# DI_DO.net
KiCad netlist of a schematic drawn in Altium Designer
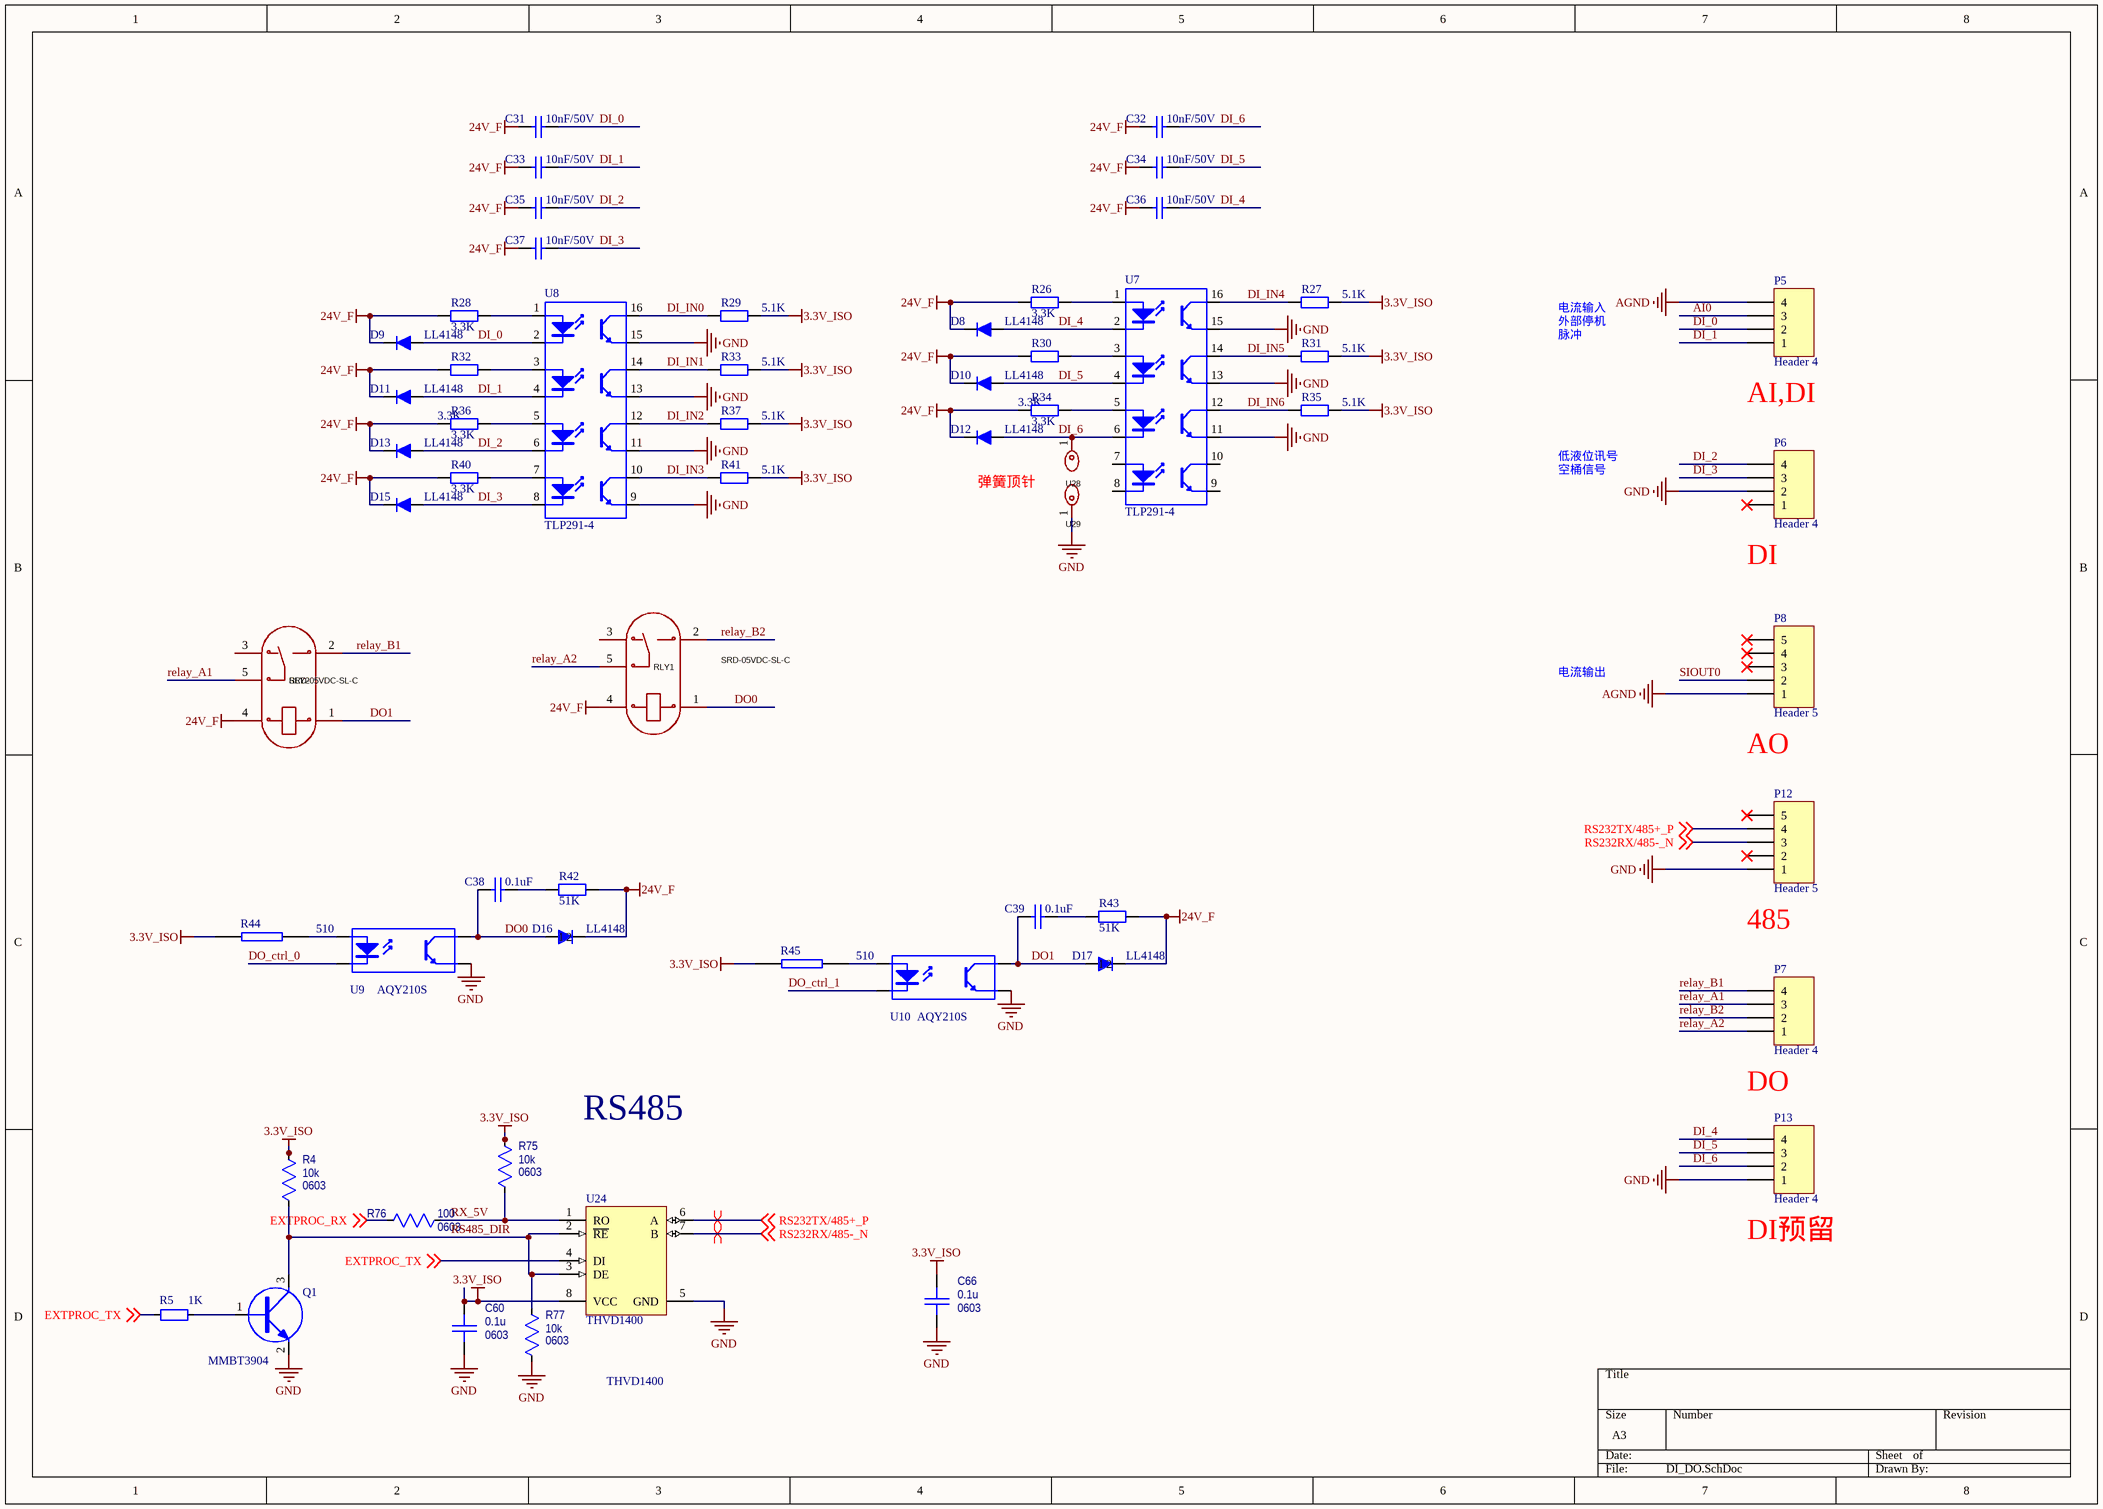
[diagram p0: DI_DO.SchDoc]

(export (version "E")
  (design (tool "Eeschema 10.0.6"))
  (components
    (comp (ref "C31")
      (value "10nF/50V")
      (footprint "0603C")
      (description "Capacitor")
      (fields (field (name "PUBLISHER") "Altium Limited"))
      (libsource (lib "Miscellaneous Devices") (part "Cap"))
    )
    (comp (ref "C32")
      (value "10nF/50V")
      (footprint "0603C")
      (description "Capacitor")
      (fields (field (name "PUBLISHER") "Altium Limited"))
      (libsource (lib "Miscellaneous Devices") (part "Cap"))
    )
    (comp (ref "C33")
      (value "10nF/50V")
      (footprint "0603C")
      (description "Capacitor")
      (fields (field (name "PUBLISHER") "Altium Limited"))
      (libsource (lib "Miscellaneous Devices") (part "Cap"))
    )
    (comp (ref "C34")
      (value "10nF/50V")
      (footprint "0603C")
      (description "Capacitor")
      (fields (field (name "PUBLISHER") "Altium Limited"))
      (libsource (lib "Miscellaneous Devices") (part "Cap"))
    )
    (comp (ref "C35")
      (value "10nF/50V")
      (footprint "0603C")
      (description "Capacitor")
      (fields (field (name "PUBLISHER") "Altium Limited"))
      (libsource (lib "Miscellaneous Devices") (part "Cap"))
    )
    (comp (ref "C36")
      (value "10nF/50V")
      (footprint "0603C")
      (description "Capacitor")
      (fields (field (name "PUBLISHER") "Altium Limited"))
      (libsource (lib "Miscellaneous Devices") (part "Cap"))
    )
    (comp (ref "C37")
      (value "10nF/50V")
      (footprint "0603C")
      (description "Capacitor")
      (fields (field (name "PUBLISHER") "Altium Limited"))
      (libsource (lib "Miscellaneous Devices") (part "Cap"))
    )
    (comp (ref "C38")
      (value "0.1uF")
      (footprint "0603C")
      (description "Capacitor")
      (libsource (lib "*") (part "CAP"))
    )
    (comp (ref "C39")
      (value "0.1uF")
      (footprint "0603C")
      (description "Capacitor")
      (libsource (lib "*") (part "CAP"))
    )
    (comp (ref "C60")
      (value "0.1u")
      (footprint "CAPC1608X092N_0603")
      (description "Capacitor, MLCC")
      (fields
        (field (name "PARTNUMBER") "C0603C104M5RACTU")
        (field (name "TOLERANCE") "[tol]")
        (field (name "PACKAGE") "0603")
      )
      (libsource (lib "Karl") (part "Capacitor_0603"))
    )
    (comp (ref "C66")
      (value "0.1u")
      (footprint "CAPC1608X092N_0603")
      (description "Capacitor, MLCC")
      (fields
        (field (name "PARTNUMBER") "C0603C104M5RACTU")
        (field (name "TOLERANCE") "[tol]")
        (field (name "PACKAGE") "0603")
      )
      (libsource (lib "Karl") (part "Capacitor_0603"))
    )
    (comp (ref "D8")
      (value "LL4148")
      (footprint "DO-213AB/LL34/MiniMELF")
      (description "VISHAY,LL4148,圆柱体MiniMELF100V/2A,ROHS")
      (libsource (lib "Device2018") (part "LL4148"))
    )
    (comp (ref "D9")
      (value "LL4148")
      (footprint "DO-213AB/LL34/MiniMELF")
      (description "VISHAY,LL4148,圆柱体MiniMELF100V/2A,ROHS")
      (libsource (lib "Device2018") (part "LL4148"))
    )
    (comp (ref "D10")
      (value "LL4148")
      (footprint "DO-213AB/LL34/MiniMELF")
      (description "VISHAY,LL4148,圆柱体MiniMELF100V/2A,ROHS")
      (libsource (lib "Device2018") (part "LL4148"))
    )
    (comp (ref "D11")
      (value "LL4148")
      (footprint "DO-213AB/LL34/MiniMELF")
      (description "VISHAY,LL4148,圆柱体MiniMELF100V/2A,ROHS")
      (libsource (lib "Device2018") (part "LL4148"))
    )
    (comp (ref "D12")
      (value "LL4148")
      (footprint "DO-213AB/LL34/MiniMELF")
      (description "VISHAY,LL4148,圆柱体MiniMELF100V/2A,ROHS")
      (libsource (lib "Device2018") (part "LL4148"))
    )
    (comp (ref "D13")
      (value "LL4148")
      (footprint "DO-213AB/LL34/MiniMELF")
      (description "VISHAY,LL4148,圆柱体MiniMELF100V/2A,ROHS")
      (libsource (lib "Device2018") (part "LL4148"))
    )
    (comp (ref "D15")
      (value "LL4148")
      (footprint "DO-213AB/LL34/MiniMELF")
      (description "VISHAY,LL4148,圆柱体MiniMELF100V/2A,ROHS")
      (libsource (lib "Device2018") (part "LL4148"))
    )
    (comp (ref "D16")
      (value "LL4148")
      (footprint "DO-213AB/LL34/MiniMELF")
      (description "VISHAY,LL4148,圆柱体MiniMELF100V/2A,ROHS")
      (libsource (lib "") (part "LL4148_1"))
    )
    (comp (ref "D17")
      (value "LL4148")
      (footprint "DO-213AB/LL34/MiniMELF")
      (description "VISHAY,LL4148,圆柱体MiniMELF100V/2A,ROHS")
      (libsource (lib "") (part "LL4148_1"))
    )
    (comp (ref "P5")
      (value "Header 4")
      (footprint "CONN#PH2.0-4A")
      (description "Header, 4-Pin")
      (fields (field (name "PUBLISHER") "Altium Limited"))
      (libsource (lib "Miscellaneous Connectors") (part "Header 4"))
    )
    (comp (ref "P6")
      (value "Header 4")
      (footprint "CONN#PH2.0-4A")
      (description "Header, 4-Pin")
      (fields (field (name "PUBLISHER") "Altium Limited"))
      (libsource (lib "Miscellaneous Connectors") (part "Header 4"))
    )
    (comp (ref "P7")
      (value "Header 4")
      (footprint "CONN#PH2.0-4A")
      (description "Header, 4-Pin")
      (fields (field (name "PUBLISHER") "Altium Limited"))
      (libsource (lib "Miscellaneous Connectors") (part "Header 4"))
    )
    (comp (ref "P8")
      (value "Header 5")
      (footprint "CONN#PH2.0-5A")
      (description "Header, 5-Pin")
      (fields (field (name "PUBLISHER") "Altium Limited"))
      (libsource (lib "Miscellaneous Connectors") (part "Header 5"))
    )
    (comp (ref "P12")
      (value "Header 5")
      (footprint "CONN#PH2.0-5A")
      (description "Header, 5-Pin")
      (fields (field (name "PUBLISHER") "Altium Limited"))
      (libsource (lib "Miscellaneous Connectors") (part "Header 5"))
    )
    (comp (ref "P13")
      (value "Header 4")
      (footprint "CONN#PH2.0-4A")
      (description "Header, 4-Pin")
      (fields (field (name "PUBLISHER") "Altium Limited"))
      (libsource (lib "Miscellaneous Connectors") (part "Header 4"))
    )
    (comp (ref "Q1")
      (value "MMBT3904")
      (footprint "SOT23-3")
      (libsource (lib "CenLib") (part "NPN_MMBT3904"))
    )
    (comp (ref "R4")
      (value "10k")
      (footprint "RESC1608X055N_0603")
      (description "Resistor, Standard")
      (fields
        (field (name "PARTNUMBER") "RC0603FR-0710KL")
        (field (name "TOLERANCE") "tol")
        (field (name "PACKAGE") "0603")
      )
      (libsource (lib "Karl") (part "Resistor_0603"))
    )
    (comp (ref "R5") (value "1K") (footprint "0603r") (libsource (lib "RC_M_D_00") (part "RES0603")))
    (comp (ref "R26") (value "3.3K") (footprint "0603R") (libsource (lib "MQlibrary") (part "Res0805M")))
    (comp (ref "R27") (value "5.1K") (footprint "0603R") (libsource (lib "MQlibrary") (part "Res0805M")))
    (comp (ref "R28") (value "3.3K") (footprint "0603R") (libsource (lib "MQlibrary") (part "Res0805M")))
    (comp (ref "R29") (value "5.1K") (footprint "0603R") (libsource (lib "MQlibrary") (part "Res0805M")))
    (comp (ref "R30") (value "3.3K") (footprint "0603R") (libsource (lib "MQlibrary") (part "Res0805M")))
    (comp (ref "R31") (value "5.1K") (footprint "0603R") (libsource (lib "MQlibrary") (part "Res0805M")))
    (comp (ref "R32") (value "3.3K") (footprint "0603R") (libsource (lib "MQlibrary") (part "Res0805M")))
    (comp (ref "R33") (value "5.1K") (footprint "0603R") (libsource (lib "MQlibrary") (part "Res0805M")))
    (comp (ref "R34") (value "3.3K") (footprint "0603R") (libsource (lib "MQlibrary") (part "Res0805M")))
    (comp (ref "R35") (value "5.1K") (footprint "0603R") (libsource (lib "MQlibrary") (part "Res0805M")))
    (comp (ref "R36") (value "3.3K") (footprint "0603R") (libsource (lib "MQlibrary") (part "Res0805M")))
    (comp (ref "R37") (value "5.1K") (footprint "0603R") (libsource (lib "MQlibrary") (part "Res0805M")))
    (comp (ref "R40") (value "3.3K") (footprint "0603R") (libsource (lib "MQlibrary") (part "Res0805M")))
    (comp (ref "R41") (value "5.1K") (footprint "0603R") (libsource (lib "MQlibrary") (part "Res0805M")))
    (comp (ref "R42") (value "51K") (footprint "0603R") (libsource (lib "") (part "Res0805M_1")))
    (comp (ref "R43") (value "51K") (footprint "0603R") (libsource (lib "") (part "Res0805M_1")))
    (comp (ref "R44") (value "510") (footprint "0603R") (libsource (lib "*") (part "RES2")))
    (comp (ref "R45") (value "510") (footprint "0603R") (libsource (lib "*") (part "RES2")))
    (comp (ref "R75")
      (value "10k")
      (footprint "RESC1608X055N_0603")
      (description "Resistor, Standard")
      (fields
        (field (name "PARTNUMBER") "RC0603FR-0710KL")
        (field (name "TOLERANCE") "tol")
        (field (name "PACKAGE") "0603")
      )
      (libsource (lib "Karl") (part "Resistor_0603"))
    )
    (comp (ref "R76")
      (value "100")
      (footprint "RESC1608X055N_0603")
      (description "Resistor, Standard")
      (fields
        (field (name "PARTNUMBER") "RC0603FR-07100RL")
        (field (name "TOLERANCE") "tol")
        (field (name "PACKAGE") "0603")
      )
      (libsource (lib "Karl") (part "Resistor_0603"))
    )
    (comp (ref "R77")
      (value "10k")
      (footprint "RESC1608X055N_0603")
      (description "Resistor, Standard")
      (fields
        (field (name "PARTNUMBER") "RC0603FR-0710KL")
        (field (name "TOLERANCE") "tol")
        (field (name "PACKAGE") "0603")
      )
      (libsource (lib "Karl") (part "Resistor_0603"))
    )
    (comp (ref "RLY1")
      (value "SRD-05VDC-SL-C")
      (footprint "RELAY-TH_SRD-XXVDC-XL-C")
      (fields (field (name "MANUFACTURER") "松乐"))
      (libsource (lib "altium-import") (part "root_0_SRD-05VDC-SL-C_"))
    )
    (comp (ref "RLY2")
      (value "SRD-05VDC-SL-C")
      (footprint "RELAY-TH_SRD-XXVDC-XL-C")
      (fields (field (name "MANUFACTURER") "松乐"))
      (libsource (lib "altium-import") (part "root_0_SRD-05VDC-SL-C_"))
    )
    (comp (ref "U7") (value "TLP291-4") (footprint "SOP16-T") (libsource (lib "DI16") (part "TLP281-4")))
    (comp (ref "U8") (value "TLP291-4") (footprint "SOP16-T") (libsource (lib "DI16") (part "TLP281-4")))
    (comp (ref "U9")
      (value "AQY210S")
      (footprint "sop4")
      (description "4-Pin Phototransistor Optocoupler")
      (fields (field (name "PUBLISHER") "Altium Limited"))
      (libsource (lib "Miscellaneous Devices") (part "Optoisolator1"))
    )
    (comp (ref "U10")
      (value "AQY210S")
      (footprint "sop4")
      (description "4-Pin Phototransistor Optocoupler")
      (fields (field (name "PUBLISHER") "Altium Limited"))
      (libsource (lib "Miscellaneous Devices") (part "Optoisolator1"))
    )
    (comp (ref "U24")
      (value "THVD1400")
      (footprint "MAXM-S8+4_M")
      (fields (field (name "PARTNUMBER") "MAX33071EASA+"))
      (libsource (lib "Bogen") (part "MAX33071EASA+"))
    )
    (comp (ref "U28")
      (value "YTC1P-3015-01")
      (footprint "CONN-SMD_YTC1P-3015-01")
      (fields (field (name "MANUFACTURER") "YIYUAN(怡远)"))
      (libsource (lib "Flow_Pump") (part "YTC1P-3015-01"))
    )
    (comp (ref "U29")
      (value "YTC1P-3015-01")
      (footprint "CONN-SMD_YTC1P-3015-01")
      (fields (field (name "MANUFACTURER") "YIYUAN(怡远)"))
      (libsource (lib "Flow_Pump") (part "YTC1P-3015-01"))
    )
  )
  (nets
    (net (code "1") (name "/AI0") (class "Default")
      (node (ref "P5") (pin "3") (pinfunction "3_3") (pintype "passive"))
    )
    (net (code "2") (name "/DI_0") (class "Default")
      (node (ref "C31") (pin "2") (pinfunction "2_2") (pintype "passive"))
      (node (ref "D9") (pin "1") (pinfunction "2_1") (pintype "passive"))
      (node (ref "P5") (pin "2") (pinfunction "2_2") (pintype "passive"))
      (node (ref "U8") (pin "2") (pinfunction "K_2") (pintype "passive"))
    )
    (net (code "3") (name "/DI_1") (class "Default")
      (node (ref "C33") (pin "2") (pinfunction "2_2") (pintype "passive"))
      (node (ref "D11") (pin "1") (pinfunction "2_1") (pintype "passive"))
      (node (ref "P5") (pin "1") (pinfunction "1_1") (pintype "passive"))
      (node (ref "U8") (pin "4") (pinfunction "K_4") (pintype "passive"))
    )
    (net (code "4") (name "/DI_2") (class "Default")
      (node (ref "C35") (pin "2") (pinfunction "2_2") (pintype "passive"))
      (node (ref "D13") (pin "1") (pinfunction "2_1") (pintype "passive"))
      (node (ref "P6") (pin "4") (pinfunction "4_4") (pintype "passive"))
      (node (ref "U8") (pin "6") (pinfunction "K_6") (pintype "passive"))
    )
    (net (code "5") (name "/DI_3") (class "Default")
      (node (ref "C37") (pin "2") (pinfunction "2_2") (pintype "passive"))
      (node (ref "D15") (pin "1") (pinfunction "2_1") (pintype "passive"))
      (node (ref "P6") (pin "3") (pinfunction "3_3") (pintype "passive"))
      (node (ref "U8") (pin "8") (pinfunction "K_8") (pintype "passive"))
    )
    (net (code "6") (name "/DI_4") (class "Default")
      (node (ref "C36") (pin "2") (pinfunction "2_2") (pintype "passive"))
      (node (ref "D8") (pin "1") (pinfunction "2_1") (pintype "passive"))
      (node (ref "P13") (pin "4") (pinfunction "4_4") (pintype "passive"))
      (node (ref "U7") (pin "2") (pinfunction "K_2") (pintype "passive"))
    )
    (net (code "7") (name "/DI_5") (class "Default")
      (node (ref "C34") (pin "2") (pinfunction "2_2") (pintype "passive"))
      (node (ref "D10") (pin "1") (pinfunction "2_1") (pintype "passive"))
      (node (ref "P13") (pin "3") (pinfunction "3_3") (pintype "passive"))
      (node (ref "U7") (pin "4") (pinfunction "K_4") (pintype "passive"))
    )
    (net (code "8") (name "/DI_6") (class "Default")
      (node (ref "C32") (pin "2") (pinfunction "2_2") (pintype "passive"))
      (node (ref "D12") (pin "1") (pinfunction "2_1") (pintype "passive"))
      (node (ref "P13") (pin "2") (pinfunction "2_2") (pintype "passive"))
      (node (ref "U28") (pin "1") (pinfunction "1_1") (pintype "passive"))
      (node (ref "U7") (pin "6") (pinfunction "K_6") (pintype "passive"))
    )
    (net (code "9") (name "/DI_IN0") (class "Default")
      (node (ref "R29") (pin "2") (pinfunction "2_2") (pintype "passive"))
      (node (ref "U8") (pin "16") (pinfunction "C_16") (pintype "passive"))
    )
    (net (code "10") (name "/DI_IN1") (class "Default")
      (node (ref "R33") (pin "2") (pinfunction "2_2") (pintype "passive"))
      (node (ref "U8") (pin "14") (pinfunction "C_14") (pintype "passive"))
    )
    (net (code "11") (name "/DI_IN2") (class "Default")
      (node (ref "R37") (pin "2") (pinfunction "2_2") (pintype "passive"))
      (node (ref "U8") (pin "12") (pinfunction "C_12") (pintype "passive"))
    )
    (net (code "12") (name "/DI_IN3") (class "Default")
      (node (ref "R41") (pin "2") (pinfunction "2_2") (pintype "passive"))
      (node (ref "U8") (pin "10") (pinfunction "C_10") (pintype "passive"))
    )
    (net (code "13") (name "/DI_IN4") (class "Default")
      (node (ref "R27") (pin "2") (pinfunction "2_2") (pintype "passive"))
      (node (ref "U7") (pin "16") (pinfunction "C_16") (pintype "passive"))
    )
    (net (code "14") (name "/DI_IN5") (class "Default")
      (node (ref "R31") (pin "2") (pinfunction "2_2") (pintype "passive"))
      (node (ref "U7") (pin "14") (pinfunction "C_14") (pintype "passive"))
    )
    (net (code "15") (name "/DI_IN6") (class "Default")
      (node (ref "R35") (pin "2") (pinfunction "2_2") (pintype "passive"))
      (node (ref "U7") (pin "12") (pinfunction "C_12") (pintype "passive"))
    )
    (net (code "16") (name "/DO0") (class "Default")
      (node (ref "C38") (pin "1") (pinfunction "1_1") (pintype "passive"))
      (node (ref "D16") (pin "1") (pinfunction "2_1") (pintype "passive"))
      (node (ref "RLY1") (pin "1") (pinfunction "1_1") (pintype "passive"))
      (node (ref "U9") (pin "4") (pinfunction "C_4") (pintype "passive"))
    )
    (net (code "17") (name "/DO1") (class "Default")
      (node (ref "C39") (pin "1") (pinfunction "1_1") (pintype "passive"))
      (node (ref "D17") (pin "1") (pinfunction "2_1") (pintype "passive"))
      (node (ref "RLY2") (pin "1") (pinfunction "1_1") (pintype "passive"))
      (node (ref "U10") (pin "4") (pinfunction "C_4") (pintype "passive"))
    )
    (net (code "18") (name "/DO_ctrl_0") (class "Default")
      (node (ref "U9") (pin "2") (pinfunction "K_2") (pintype "passive"))
    )
    (net (code "19") (name "/DO_ctrl_1") (class "Default")
      (node (ref "U10") (pin "2") (pinfunction "K_2") (pintype "passive"))
    )
    (net (code "20") (name "/RS485_DIR") (class "Default")
      (node (ref "Q1") (pin "3") (pinfunction "C_3") (pintype "passive"))
      (node (ref "R4") (pin "1") (pinfunction "1_1") (pintype "passive"))
      (node (ref "R77") (pin "2") (pinfunction "2_2") (pintype "passive"))
      (node (ref "U24") (pin "2") (pinfunction "~{RE}_2") (pintype "input"))
      (node (ref "U24") (pin "3") (pinfunction "DE_3") (pintype "input"))
    )
    (net (code "21") (name "/RX_5V") (class "Default")
      (node (ref "R75") (pin "1") (pinfunction "1_1") (pintype "passive"))
      (node (ref "R76") (pin "1") (pinfunction "1_1") (pintype "passive"))
      (node (ref "U24") (pin "1") (pinfunction "RO_1") (pintype "tri_state"))
    )
    (net (code "22") (name "/SIOUT0") (class "Default")
      (node (ref "P8") (pin "2") (pinfunction "2_2") (pintype "passive"))
    )
    (net (code "23") (name "/relay_A1") (class "Default")
      (node (ref "P7") (pin "3") (pinfunction "3_3") (pintype "passive"))
      (node (ref "RLY2") (pin "5") (pinfunction "5_5") (pintype "passive"))
    )
    (net (code "24") (name "/relay_A2") (class "Default")
      (node (ref "P7") (pin "1") (pinfunction "1_1") (pintype "passive"))
      (node (ref "RLY1") (pin "5") (pinfunction "5_5") (pintype "passive"))
    )
    (net (code "25") (name "/relay_B1") (class "Default")
      (node (ref "P7") (pin "4") (pinfunction "4_4") (pintype "passive"))
      (node (ref "RLY2") (pin "2") (pinfunction "2_2") (pintype "passive"))
    )
    (net (code "26") (name "/relay_B2") (class "Default")
      (node (ref "P7") (pin "2") (pinfunction "2_2") (pintype "passive"))
      (node (ref "RLY1") (pin "2") (pinfunction "2_2") (pintype "passive"))
    )
    (net (code "27") (name "3.3V_ISO") (class "Default")
      (node (ref "C60") (pin "1") (pinfunction "1_1") (pintype "passive"))
      (node (ref "C66") (pin "1") (pinfunction "1_1") (pintype "passive"))
      (node (ref "R27") (pin "1") (pinfunction "1_1") (pintype "passive"))
      (node (ref "R29") (pin "1") (pinfunction "1_1") (pintype "passive"))
      (node (ref "R31") (pin "1") (pinfunction "1_1") (pintype "passive"))
      (node (ref "R33") (pin "1") (pinfunction "1_1") (pintype "passive"))
      (node (ref "R35") (pin "1") (pinfunction "1_1") (pintype "passive"))
      (node (ref "R37") (pin "1") (pinfunction "1_1") (pintype "passive"))
      (node (ref "R4") (pin "2") (pinfunction "2_2") (pintype "passive"))
      (node (ref "R41") (pin "1") (pinfunction "1_1") (pintype "passive"))
      (node (ref "R44") (pin "2") (pinfunction "2_2") (pintype "passive"))
      (node (ref "R45") (pin "2") (pinfunction "2_2") (pintype "passive"))
      (node (ref "R75") (pin "2") (pinfunction "2_2") (pintype "passive"))
      (node (ref "U24") (pin "8") (pinfunction "VCC_8") (pintype "power_in"))
    )
    (net (code "28") (name "24V_F") (class "Default")
      (node (ref "C31") (pin "1") (pinfunction "1_1") (pintype "passive"))
      (node (ref "C32") (pin "1") (pinfunction "1_1") (pintype "passive"))
      (node (ref "C33") (pin "1") (pinfunction "1_1") (pintype "passive"))
      (node (ref "C34") (pin "1") (pinfunction "1_1") (pintype "passive"))
      (node (ref "C35") (pin "1") (pinfunction "1_1") (pintype "passive"))
      (node (ref "C36") (pin "1") (pinfunction "1_1") (pintype "passive"))
      (node (ref "C37") (pin "1") (pinfunction "1_1") (pintype "passive"))
      (node (ref "D10") (pin "2") (pinfunction "1_2") (pintype "passive"))
      (node (ref "D11") (pin "2") (pinfunction "1_2") (pintype "passive"))
      (node (ref "D12") (pin "2") (pinfunction "1_2") (pintype "passive"))
      (node (ref "D13") (pin "2") (pinfunction "1_2") (pintype "passive"))
      (node (ref "D15") (pin "2") (pinfunction "1_2") (pintype "passive"))
      (node (ref "D16") (pin "2") (pinfunction "1_2") (pintype "passive"))
      (node (ref "D17") (pin "2") (pinfunction "1_2") (pintype "passive"))
      (node (ref "D8") (pin "2") (pinfunction "1_2") (pintype "passive"))
      (node (ref "D9") (pin "2") (pinfunction "1_2") (pintype "passive"))
      (node (ref "R26") (pin "2") (pinfunction "2_2") (pintype "passive"))
      (node (ref "R28") (pin "2") (pinfunction "2_2") (pintype "passive"))
      (node (ref "R30") (pin "2") (pinfunction "2_2") (pintype "passive"))
      (node (ref "R32") (pin "2") (pinfunction "2_2") (pintype "passive"))
      (node (ref "R34") (pin "2") (pinfunction "2_2") (pintype "passive"))
      (node (ref "R36") (pin "2") (pinfunction "2_2") (pintype "passive"))
      (node (ref "R40") (pin "2") (pinfunction "2_2") (pintype "passive"))
      (node (ref "R42") (pin "2") (pinfunction "2_2") (pintype "passive"))
      (node (ref "R43") (pin "2") (pinfunction "2_2") (pintype "passive"))
      (node (ref "RLY1") (pin "4") (pinfunction "4_4") (pintype "passive"))
      (node (ref "RLY2") (pin "4") (pinfunction "4_4") (pintype "passive"))
    )
    (net (code "29") (name "AGND") (class "Default")
      (node (ref "P5") (pin "4") (pinfunction "4_4") (pintype "passive"))
      (node (ref "P8") (pin "1") (pinfunction "1_1") (pintype "passive"))
    )
    (net (code "30") (name "EXTPROC_RX") (class "Default")
      (node (ref "R76") (pin "2") (pinfunction "2_2") (pintype "passive"))
    )
    (net (code "31") (name "EXTPROC_TX") (class "Default")
      (node (ref "R5") (pin "1") (pinfunction "1_1") (pintype "passive"))
      (node (ref "U24") (pin "4") (pinfunction "DI_4") (pintype "input"))
    )
    (net (code "32") (name "GND") (class "Default")
      (node (ref "C60") (pin "2") (pinfunction "2_2") (pintype "passive"))
      (node (ref "C66") (pin "2") (pinfunction "2_2") (pintype "passive"))
      (node (ref "P12") (pin "1") (pinfunction "1_1") (pintype "passive"))
      (node (ref "P13") (pin "1") (pinfunction "1_1") (pintype "passive"))
      (node (ref "P6") (pin "2") (pinfunction "2_2") (pintype "passive"))
      (node (ref "Q1") (pin "2") (pinfunction "E_2") (pintype "passive"))
      (node (ref "R77") (pin "1") (pinfunction "1_1") (pintype "passive"))
      (node (ref "U10") (pin "3") (pinfunction "E_3") (pintype "passive"))
      (node (ref "U24") (pin "5") (pinfunction "GND_5") (pintype "power_in"))
      (node (ref "U29") (pin "1") (pinfunction "1_1") (pintype "passive"))
      (node (ref "U7") (pin "11") (pinfunction "E_11") (pintype "passive"))
      (node (ref "U7") (pin "13") (pinfunction "E_13") (pintype "passive"))
      (node (ref "U7") (pin "15") (pinfunction "E_15") (pintype "passive"))
      (node (ref "U8") (pin "11") (pinfunction "E_11") (pintype "passive"))
      (node (ref "U8") (pin "13") (pinfunction "E_13") (pintype "passive"))
      (node (ref "U8") (pin "15") (pinfunction "E_15") (pintype "passive"))
      (node (ref "U8") (pin "9") (pinfunction "E_9") (pintype "passive"))
      (node (ref "U9") (pin "3") (pinfunction "E_3") (pintype "passive"))
    )
    (net (code "33") (name "Net-(C38-Pad2)") (class "Default")
      (node (ref "C38") (pin "2") (pinfunction "2_2") (pintype "passive"))
      (node (ref "R42") (pin "1") (pinfunction "1_1") (pintype "passive"))
    )
    (net (code "34") (name "Net-(C39-Pad2)") (class "Default")
      (node (ref "C39") (pin "2") (pinfunction "2_2") (pintype "passive"))
      (node (ref "R43") (pin "1") (pinfunction "1_1") (pintype "passive"))
    )
    (net (code "35") (name "Net-(Q1-B)") (class "Default")
      (node (ref "Q1") (pin "1") (pinfunction "B_1") (pintype "passive"))
      (node (ref "R5") (pin "2") (pinfunction "2_2") (pintype "passive"))
    )
    (net (code "36") (name "Net-(R26-Pad1)") (class "Default")
      (node (ref "R26") (pin "1") (pinfunction "1_1") (pintype "passive"))
      (node (ref "U7") (pin "1") (pinfunction "A_1") (pintype "passive"))
    )
    (net (code "37") (name "Net-(R28-Pad1)") (class "Default")
      (node (ref "R28") (pin "1") (pinfunction "1_1") (pintype "passive"))
      (node (ref "U8") (pin "1") (pinfunction "A_1") (pintype "passive"))
    )
    (net (code "38") (name "Net-(R30-Pad1)") (class "Default")
      (node (ref "R30") (pin "1") (pinfunction "1_1") (pintype "passive"))
      (node (ref "U7") (pin "3") (pinfunction "A_3") (pintype "passive"))
    )
    (net (code "39") (name "Net-(R32-Pad1)") (class "Default")
      (node (ref "R32") (pin "1") (pinfunction "1_1") (pintype "passive"))
      (node (ref "U8") (pin "3") (pinfunction "A_3") (pintype "passive"))
    )
    (net (code "40") (name "Net-(R34-Pad1)") (class "Default")
      (node (ref "R34") (pin "1") (pinfunction "1_1") (pintype "passive"))
      (node (ref "U7") (pin "5") (pinfunction "A_5") (pintype "passive"))
    )
    (net (code "41") (name "Net-(R36-Pad1)") (class "Default")
      (node (ref "R36") (pin "1") (pinfunction "1_1") (pintype "passive"))
      (node (ref "U8") (pin "5") (pinfunction "A_5") (pintype "passive"))
    )
    (net (code "42") (name "Net-(R40-Pad1)") (class "Default")
      (node (ref "R40") (pin "1") (pinfunction "1_1") (pintype "passive"))
      (node (ref "U8") (pin "7") (pinfunction "A_7") (pintype "passive"))
    )
    (net (code "43") (name "Net-(U9-A)") (class "Default")
      (node (ref "R44") (pin "1") (pinfunction "1_1") (pintype "passive"))
      (node (ref "U9") (pin "1") (pinfunction "A_1") (pintype "passive"))
    )
    (net (code "44") (name "Net-(U10-A)") (class "Default")
      (node (ref "R45") (pin "1") (pinfunction "1_1") (pintype "passive"))
      (node (ref "U10") (pin "1") (pinfunction "A_1") (pintype "passive"))
    )
    (net (code "45") (name "RS232RX{slash}485-_N") (class "Default")
      (node (ref "P12") (pin "3") (pinfunction "3_3") (pintype "passive"))
      (node (ref "U24") (pin "7") (pinfunction "B_7") (pintype "bidirectional"))
    )
    (net (code "46") (name "RS232TX{slash}485+_P") (class "Default")
      (node (ref "P12") (pin "4") (pinfunction "4_4") (pintype "passive"))
      (node (ref "U24") (pin "6") (pinfunction "A_6") (pintype "bidirectional"))
    )
    (net (code "47") (name "unconnected-(P6-Pad1)") (class "Default")
      (node (ref "P6") (pin "1") (pinfunction "1_1") (pintype "passive+no_connect"))
    )
    (net (code "48") (name "unconnected-(P8-Pad3)") (class "Default")
      (node (ref "P8") (pin "3") (pinfunction "3_3") (pintype "passive+no_connect"))
    )
    (net (code "49") (name "unconnected-(P8-Pad4)") (class "Default")
      (node (ref "P8") (pin "4") (pinfunction "4_4") (pintype "passive+no_connect"))
    )
    (net (code "50") (name "unconnected-(P8-Pad5)") (class "Default")
      (node (ref "P8") (pin "5") (pinfunction "5_5") (pintype "passive+no_connect"))
    )
    (net (code "51") (name "unconnected-(P12-Pad2)") (class "Default")
      (node (ref "P12") (pin "2") (pinfunction "2_2") (pintype "passive+no_connect"))
    )
    (net (code "52") (name "unconnected-(P12-Pad5)") (class "Default")
      (node (ref "P12") (pin "5") (pinfunction "5_5") (pintype "passive+no_connect"))
    )
    (net (code "53") (name "unconnected-(RLY1-Pad3)") (class "Default")
      (node (ref "RLY1") (pin "3") (pinfunction "3_3") (pintype "passive"))
    )
    (net (code "54") (name "unconnected-(RLY2-Pad3)") (class "Default")
      (node (ref "RLY2") (pin "3") (pinfunction "3_3") (pintype "passive"))
    )
    (net (code "55") (name "unconnected-(U7-A-Pad7)") (class "Default")
      (node (ref "U7") (pin "7") (pinfunction "A_7") (pintype "passive"))
    )
    (net (code "56") (name "unconnected-(U7-C-Pad10)") (class "Default")
      (node (ref "U7") (pin "10") (pinfunction "C_10") (pintype "passive"))
    )
    (net (code "57") (name "unconnected-(U7-E-Pad9)") (class "Default")
      (node (ref "U7") (pin "9") (pinfunction "E_9") (pintype "passive"))
    )
    (net (code "58") (name "unconnected-(U7-K-Pad8)") (class "Default")
      (node (ref "U7") (pin "8") (pinfunction "K_8") (pintype "passive"))
    )
  )
)
